# sphinkter.net
KiCad netlist of a schematic drawn in EAGLE
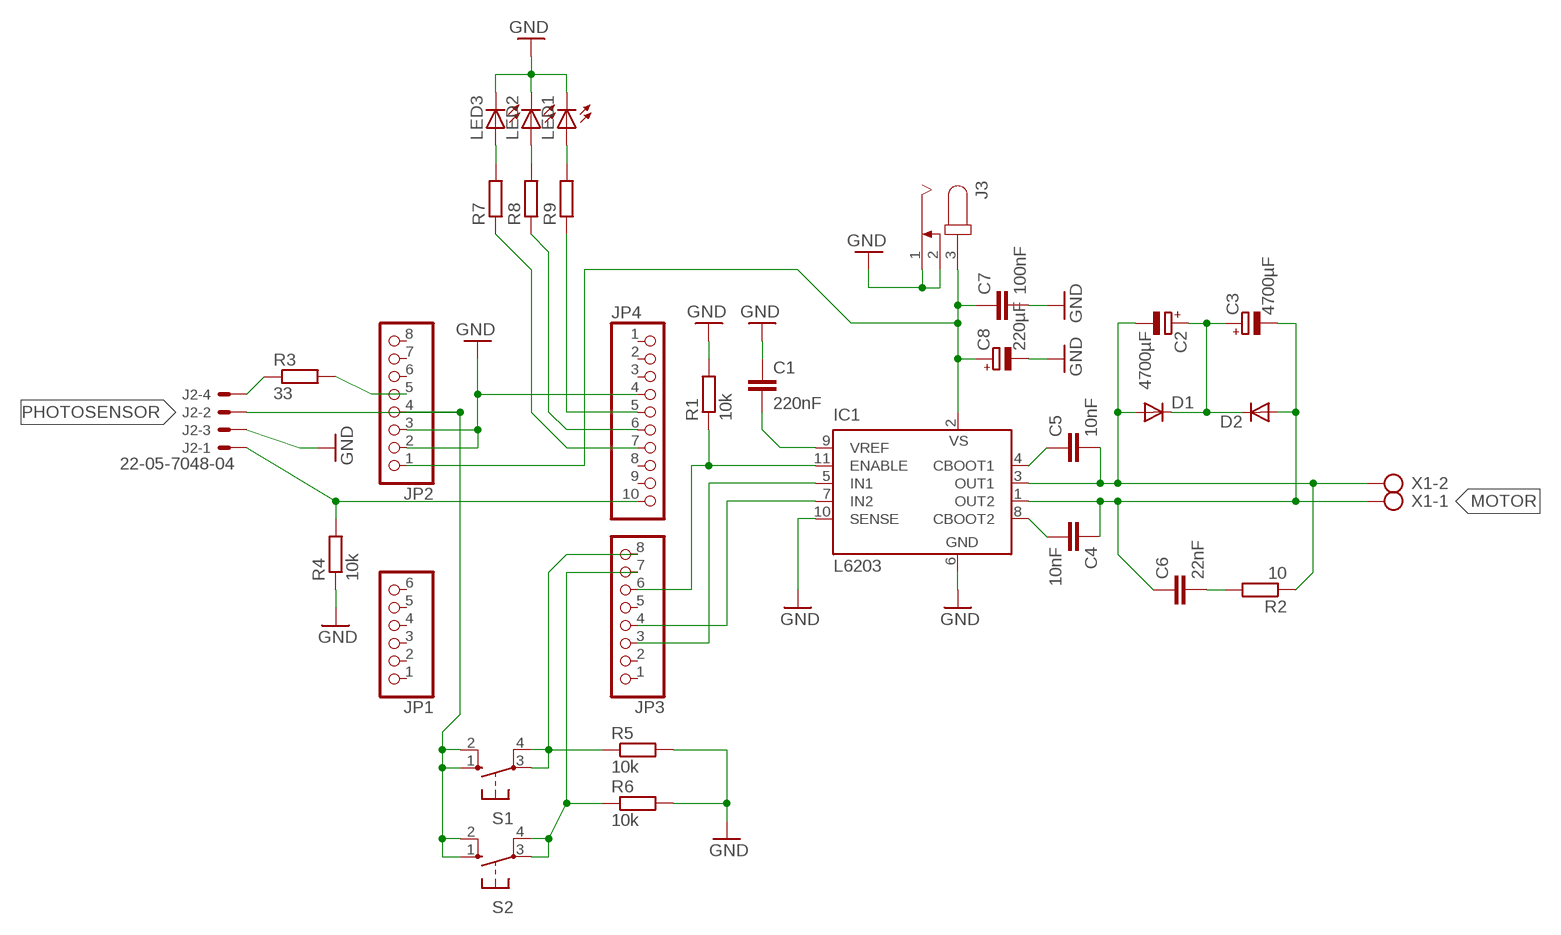
[diagram p0: schematic, sheet 1]

(export (version "E")
  (design (tool "Eeschema 10.0.6"))
  (components
    (comp (ref "C1")
      (value "220nF")
      (footprint "eagle-import:C050-024X044")
      (libsource (lib "eagle-import") (part "C-EU050-024X044"))
    )
    (comp (ref "C2")
      (value "4700µF")
      (footprint "eagle-import:E7,5-16")
      (libsource (lib "eagle-import") (part "CPOL-EUE7.5-16"))
    )
    (comp (ref "C3")
      (value "4700µF")
      (footprint "eagle-import:E7,5-16")
      (libsource (lib "eagle-import") (part "CPOL-EUE7.5-16"))
    )
    (comp (ref "C4")
      (value "10nF")
      (footprint "eagle-import:C025-025X050")
      (libsource (lib "eagle-import") (part "resistor_C-EU025-025X050"))
    )
    (comp (ref "C5")
      (value "10nF")
      (footprint "eagle-import:C025-025X050")
      (libsource (lib "eagle-import") (part "resistor_C-EU025-025X050"))
    )
    (comp (ref "C6")
      (value "22nF")
      (footprint "eagle-import:C050-024X044")
      (libsource (lib "eagle-import") (part "resistor_C-EU050-024X044"))
    )
    (comp (ref "C7")
      (value "100nF")
      (footprint "eagle-import:C050-024X044")
      (libsource (lib "eagle-import") (part "resistor_C-EU050-024X044"))
    )
    (comp (ref "C8")
      (value "220µF")
      (footprint "eagle-import:E3,5-8")
      (libsource (lib "eagle-import") (part "CPOL-EUE3.5-8"))
    )
    (comp (ref "D1")
      (value "DIODE-DO27-15")
      (footprint "eagle-import:DO27-15")
      (libsource (lib "eagle-import") (part "DIODE-DO27-15"))
    )
    (comp (ref "D2")
      (value "DIODE-DO27-15")
      (footprint "eagle-import:DO27-15")
      (libsource (lib "eagle-import") (part "DIODE-DO27-15"))
    )
    (comp (ref "IC1")
      (value "L6203")
      (footprint "eagle-import:MULTIWATT-11")
      (libsource (lib "eagle-import") (part "L6203"))
    )
    (comp (ref "J2")
      (value "22-05-7048-04")
      (footprint "eagle-import:7395-04")
      (libsource (lib "eagle-import") (part "22-?-0405-7048"))
    )
    (comp (ref "J3")
      (value "JACK-PLUG0")
      (footprint "eagle-import:SPC4077")
      (libsource (lib "eagle-import") (part "JACK-PLUG0"))
    )
    (comp (ref "JP1")
      (value "PINHD-1X6")
      (footprint "eagle-import:1X06")
      (libsource (lib "eagle-import") (part "PINHD-1X6"))
    )
    (comp (ref "JP2")
      (value "PINHD-1X8")
      (footprint "eagle-import:1X08")
      (libsource (lib "eagle-import") (part "PINHD-1X8"))
    )
    (comp (ref "JP3")
      (value "PINHD-1X8")
      (footprint "eagle-import:1X08")
      (libsource (lib "eagle-import") (part "PINHD-1X8"))
    )
    (comp (ref "JP4")
      (value "PINHD-1X10")
      (footprint "eagle-import:1X10")
      (libsource (lib "eagle-import") (part "PINHD-1X10"))
    )
    (comp (ref "LED1")
      (value "LED5MM")
      (footprint "eagle-import:LED5MM")
      (libsource (lib "eagle-import") (part "LED5MM"))
    )
    (comp (ref "LED2")
      (value "LED5MM")
      (footprint "eagle-import:LED5MM")
      (libsource (lib "eagle-import") (part "LED5MM"))
    )
    (comp (ref "LED3")
      (value "LED5MM")
      (footprint "eagle-import:LED5MM")
      (libsource (lib "eagle-import") (part "LED5MM"))
    )
    (comp (ref "R1")
      (value "10k")
      (footprint "eagle-import:0207_10")
      (libsource (lib "eagle-import") (part "R-EU_0207/10"))
    )
    (comp (ref "R2")
      (value "10")
      (footprint "eagle-import:0207_10")
      (libsource (lib "eagle-import") (part "R-EU_0207/10"))
    )
    (comp (ref "R3")
      (value "33")
      (footprint "eagle-import:0207_10")
      (libsource (lib "eagle-import") (part "R-EU_0207/10"))
    )
    (comp (ref "R4")
      (value "10k")
      (footprint "eagle-import:0207_10")
      (libsource (lib "eagle-import") (part "R-EU_0207/10"))
    )
    (comp (ref "R5")
      (value "10k")
      (footprint "eagle-import:0207_10")
      (libsource (lib "eagle-import") (part "R-EU_0207/10"))
    )
    (comp (ref "R6")
      (value "10k")
      (footprint "eagle-import:0207_10")
      (libsource (lib "eagle-import") (part "R-EU_0207/10"))
    )
    (comp (ref "R7")
      (value "R-EU_0207/10")
      (footprint "eagle-import:0207_10")
      (libsource (lib "eagle-import") (part "R-EU_0207/10"))
    )
    (comp (ref "R8")
      (value "R-EU_0207/10")
      (footprint "eagle-import:0207_10")
      (libsource (lib "eagle-import") (part "R-EU_0207/10"))
    )
    (comp (ref "R9")
      (value "R-EU_0207/10")
      (footprint "eagle-import:0207_10")
      (libsource (lib "eagle-import") (part "R-EU_0207/10"))
    )
    (comp (ref "S1")
      (value "10-XX")
      (footprint "eagle-import:B3F-10XX")
      (fields (field (name "MPN") "B3F-1000"))
      (libsource (lib "eagle-import") (part "10-XX"))
    )
    (comp (ref "S2")
      (value "10-XX")
      (footprint "eagle-import:B3F-10XX")
      (fields (field (name "MPN") "B3F-1000"))
      (libsource (lib "eagle-import") (part "10-XX"))
    )
    (comp (ref "X1")
      (value "AK500/2")
      (footprint "eagle-import:AK500_2")
      (libsource (lib "eagle-import") (part "AK500/2"))
    )
  )
  (nets
    (net (code "1") (name "GND") (class "Default")
      (node (ref "C1") (pin "1") (pinfunction "1_1") (pintype "passive"))
      (node (ref "C7") (pin "2") (pinfunction "2_2") (pintype "passive"))
      (node (ref "C8") (pin "-") (pinfunction "-_-") (pintype "passive"))
      (node (ref "IC1") (pin "10") (pinfunction "SENSE_10") (pintype "input"))
      (node (ref "IC1") (pin "6") (pinfunction "GND_6") (pintype "power_in"))
      (node (ref "J2") (pin "3") (pinfunction "S_3") (pintype "passive"))
      (node (ref "J3") (pin "1") (pinfunction "1_1") (pintype "passive"))
      (node (ref "J3") (pin "2") (pinfunction "2_2") (pintype "passive"))
      (node (ref "JP2") (pin "2") (pinfunction "2_2") (pintype "passive"))
      (node (ref "JP2") (pin "3") (pinfunction "3_3") (pintype "passive"))
      (node (ref "JP4") (pin "4") (pinfunction "4_4") (pintype "passive"))
      (node (ref "LED1") (pin "K") (pinfunction "C_K") (pintype "passive"))
      (node (ref "LED2") (pin "K") (pinfunction "C_K") (pintype "passive"))
      (node (ref "LED3") (pin "K") (pinfunction "C_K") (pintype "passive"))
      (node (ref "R1") (pin "2") (pinfunction "2_2") (pintype "passive"))
      (node (ref "R4") (pin "1") (pinfunction "1_1") (pintype "passive"))
      (node (ref "R5") (pin "2") (pinfunction "2_2") (pintype "passive"))
      (node (ref "R6") (pin "2") (pinfunction "2_2") (pintype "passive"))
    )
    (net (code "2") (name "MOTOR") (class "Default")
      (node (ref "C3") (pin "-") (pinfunction "-_-") (pintype "passive"))
      (node (ref "C4") (pin "1") (pinfunction "1_1") (pintype "passive"))
      (node (ref "C6") (pin "1") (pinfunction "1_1") (pintype "passive"))
      (node (ref "D2") (pin "A") (pinfunction "A_A") (pintype "passive"))
      (node (ref "IC1") (pin "1") (pinfunction "OUT2_1") (pintype "output"))
      (node (ref "X1") (pin "1") (pinfunction "KL_1") (pintype "passive"))
    )
    (net (code "3") (name "Net-(C2-Pad+)") (class "Default")
      (node (ref "C2") (pin "+") (pinfunction "+_+") (pintype "passive"))
      (node (ref "C3") (pin "+") (pinfunction "+_+") (pintype "passive"))
      (node (ref "D1") (pin "C") (pinfunction "C_C") (pintype "passive"))
      (node (ref "D2") (pin "C") (pinfunction "C_C") (pintype "passive"))
    )
    (net (code "4") (name "Net-(C6-Pad2)") (class "Default")
      (node (ref "C6") (pin "2") (pinfunction "2_2") (pintype "passive"))
      (node (ref "R2") (pin "2") (pinfunction "2_2") (pintype "passive"))
    )
    (net (code "5") (name "Net-(IC1-CBOOT1)") (class "Default")
      (node (ref "C5") (pin "1") (pinfunction "1_1") (pintype "passive"))
      (node (ref "IC1") (pin "4") (pinfunction "CBOOT1_4") (pintype "input"))
    )
    (net (code "6") (name "Net-(IC1-CBOOT2)") (class "Default")
      (node (ref "C4") (pin "2") (pinfunction "2_2") (pintype "passive"))
      (node (ref "IC1") (pin "8") (pinfunction "CBOOT2_8") (pintype "input"))
    )
    (net (code "7") (name "Net-(IC1-ENABLE)") (class "Default")
      (node (ref "IC1") (pin "11") (pinfunction "ENABLE_11") (pintype "input"))
      (node (ref "JP3") (pin "6") (pinfunction "6_6") (pintype "passive"))
      (node (ref "R1") (pin "1") (pinfunction "1_1") (pintype "passive"))
    )
    (net (code "8") (name "Net-(IC1-IN1)") (class "Default")
      (node (ref "IC1") (pin "5") (pinfunction "IN1_5") (pintype "input"))
      (node (ref "JP3") (pin "3") (pinfunction "3_3") (pintype "passive"))
    )
    (net (code "9") (name "Net-(IC1-IN2)") (class "Default")
      (node (ref "IC1") (pin "7") (pinfunction "IN2_7") (pintype "input"))
      (node (ref "JP3") (pin "4") (pinfunction "4_4") (pintype "passive"))
    )
    (net (code "10") (name "Net-(IC1-OUT1)") (class "Default")
      (node (ref "C2") (pin "-") (pinfunction "-_-") (pintype "passive"))
      (node (ref "C5") (pin "2") (pinfunction "2_2") (pintype "passive"))
      (node (ref "D1") (pin "A") (pinfunction "A_A") (pintype "passive"))
      (node (ref "IC1") (pin "3") (pinfunction "OUT1_3") (pintype "output"))
      (node (ref "R2") (pin "1") (pinfunction "1_1") (pintype "passive"))
      (node (ref "X1") (pin "2") (pinfunction "KL_2") (pintype "passive"))
    )
    (net (code "11") (name "Net-(IC1-VREF)") (class "Default")
      (node (ref "C1") (pin "2") (pinfunction "2_2") (pintype "passive"))
      (node (ref "IC1") (pin "9") (pinfunction "VREF_9") (pintype "input"))
    )
    (net (code "12") (name "Net-(IC1-VS)") (class "Default")
      (node (ref "C7") (pin "1") (pinfunction "1_1") (pintype "passive"))
      (node (ref "C8") (pin "+") (pinfunction "+_+") (pintype "passive"))
      (node (ref "IC1") (pin "2") (pinfunction "VS_2") (pintype "power_in"))
      (node (ref "J3") (pin "3") (pinfunction "3_3") (pintype "passive"))
      (node (ref "JP2") (pin "1") (pinfunction "1_1") (pintype "passive"))
    )
    (net (code "13") (name "Net-(J2A-S)") (class "Default")
      (node (ref "J2") (pin "1") (pinfunction "S_1") (pintype "passive"))
      (node (ref "JP4") (pin "10") (pinfunction "10_10") (pintype "passive"))
      (node (ref "R4") (pin "2") (pinfunction "2_2") (pintype "passive"))
    )
    (net (code "14") (name "Net-(J2D-S)") (class "Default")
      (node (ref "J2") (pin "4") (pinfunction "S_4") (pintype "passive"))
      (node (ref "R3") (pin "1") (pinfunction "1_1") (pintype "passive"))
    )
    (net (code "15") (name "Net-(JP2-Pad5)") (class "Default")
      (node (ref "JP2") (pin "5") (pinfunction "5_5") (pintype "passive"))
      (node (ref "R3") (pin "2") (pinfunction "2_2") (pintype "passive"))
    )
    (net (code "16") (name "Net-(JP4-Pad5)") (class "Default")
      (node (ref "JP4") (pin "5") (pinfunction "5_5") (pintype "passive"))
      (node (ref "R9") (pin "1") (pinfunction "1_1") (pintype "passive"))
    )
    (net (code "17") (name "Net-(JP4-Pad6)") (class "Default")
      (node (ref "JP4") (pin "6") (pinfunction "6_6") (pintype "passive"))
      (node (ref "R8") (pin "1") (pinfunction "1_1") (pintype "passive"))
    )
    (net (code "18") (name "Net-(JP4-Pad7)") (class "Default")
      (node (ref "JP4") (pin "7") (pinfunction "7_7") (pintype "passive"))
      (node (ref "R7") (pin "1") (pinfunction "1_1") (pintype "passive"))
    )
    (net (code "19") (name "Net-(LED1-PadA)") (class "Default")
      (node (ref "LED1") (pin "A") (pinfunction "A_A") (pintype "passive"))
      (node (ref "R9") (pin "2") (pinfunction "2_2") (pintype "passive"))
    )
    (net (code "20") (name "Net-(LED2-PadA)") (class "Default")
      (node (ref "LED2") (pin "A") (pinfunction "A_A") (pintype "passive"))
      (node (ref "R8") (pin "2") (pinfunction "2_2") (pintype "passive"))
    )
    (net (code "21") (name "Net-(LED3-PadA)") (class "Default")
      (node (ref "LED3") (pin "A") (pinfunction "A_A") (pintype "passive"))
      (node (ref "R7") (pin "2") (pinfunction "2_2") (pintype "passive"))
    )
    (net (code "22") (name "Net-(S1-P)") (class "Default")
      (node (ref "JP3") (pin "8") (pinfunction "8_8") (pintype "passive"))
      (node (ref "R5") (pin "1") (pinfunction "1_1") (pintype "passive"))
      (node (ref "S1") (pin "3") (pinfunction "P_3") (pintype "passive"))
      (node (ref "S1") (pin "4") (pinfunction "P1_4") (pintype "passive"))
    )
    (net (code "23") (name "Net-(S2-P)") (class "Default")
      (node (ref "JP3") (pin "7") (pinfunction "7_7") (pintype "passive"))
      (node (ref "R6") (pin "1") (pinfunction "1_1") (pintype "passive"))
      (node (ref "S2") (pin "3") (pinfunction "P_3") (pintype "passive"))
      (node (ref "S2") (pin "4") (pinfunction "P1_4") (pintype "passive"))
    )
    (net (code "24") (name "PHOTOSENSOR") (class "Default")
      (node (ref "J2") (pin "2") (pinfunction "S_2") (pintype "passive"))
      (node (ref "JP2") (pin "4") (pinfunction "4_4") (pintype "passive"))
      (node (ref "S1") (pin "1") (pinfunction "S_1") (pintype "passive"))
      (node (ref "S1") (pin "2") (pinfunction "S1_2") (pintype "passive"))
      (node (ref "S2") (pin "1") (pinfunction "S_1") (pintype "passive"))
      (node (ref "S2") (pin "2") (pinfunction "S1_2") (pintype "passive"))
    )
    (net (code "25") (name "unconnected-(JP1-Pad1)") (class "Default")
      (node (ref "JP1") (pin "1") (pinfunction "1_1") (pintype "passive"))
    )
    (net (code "26") (name "unconnected-(JP1-Pad2)") (class "Default")
      (node (ref "JP1") (pin "2") (pinfunction "2_2") (pintype "passive"))
    )
    (net (code "27") (name "unconnected-(JP1-Pad3)") (class "Default")
      (node (ref "JP1") (pin "3") (pinfunction "3_3") (pintype "passive"))
    )
    (net (code "28") (name "unconnected-(JP1-Pad4)") (class "Default")
      (node (ref "JP1") (pin "4") (pinfunction "4_4") (pintype "passive"))
    )
    (net (code "29") (name "unconnected-(JP1-Pad5)") (class "Default")
      (node (ref "JP1") (pin "5") (pinfunction "5_5") (pintype "passive"))
    )
    (net (code "30") (name "unconnected-(JP1-Pad6)") (class "Default")
      (node (ref "JP1") (pin "6") (pinfunction "6_6") (pintype "passive"))
    )
    (net (code "31") (name "unconnected-(JP2-Pad6)") (class "Default")
      (node (ref "JP2") (pin "6") (pinfunction "6_6") (pintype "passive"))
    )
    (net (code "32") (name "unconnected-(JP2-Pad7)") (class "Default")
      (node (ref "JP2") (pin "7") (pinfunction "7_7") (pintype "passive"))
    )
    (net (code "33") (name "unconnected-(JP2-Pad8)") (class "Default")
      (node (ref "JP2") (pin "8") (pinfunction "8_8") (pintype "passive"))
    )
    (net (code "34") (name "unconnected-(JP3-Pad1)") (class "Default")
      (node (ref "JP3") (pin "1") (pinfunction "1_1") (pintype "passive"))
    )
    (net (code "35") (name "unconnected-(JP3-Pad2)") (class "Default")
      (node (ref "JP3") (pin "2") (pinfunction "2_2") (pintype "passive"))
    )
    (net (code "36") (name "unconnected-(JP3-Pad5)") (class "Default")
      (node (ref "JP3") (pin "5") (pinfunction "5_5") (pintype "passive"))
    )
    (net (code "37") (name "unconnected-(JP4-Pad1)") (class "Default")
      (node (ref "JP4") (pin "1") (pinfunction "1_1") (pintype "passive"))
    )
    (net (code "38") (name "unconnected-(JP4-Pad2)") (class "Default")
      (node (ref "JP4") (pin "2") (pinfunction "2_2") (pintype "passive"))
    )
    (net (code "39") (name "unconnected-(JP4-Pad3)") (class "Default")
      (node (ref "JP4") (pin "3") (pinfunction "3_3") (pintype "passive"))
    )
    (net (code "40") (name "unconnected-(JP4-Pad8)") (class "Default")
      (node (ref "JP4") (pin "8") (pinfunction "8_8") (pintype "passive"))
    )
    (net (code "41") (name "unconnected-(JP4-Pad9)") (class "Default")
      (node (ref "JP4") (pin "9") (pinfunction "9_9") (pintype "passive"))
    )
  )
)
